# Logic_Gates.net
KiCad netlist of a schematic drawn in EAGLE
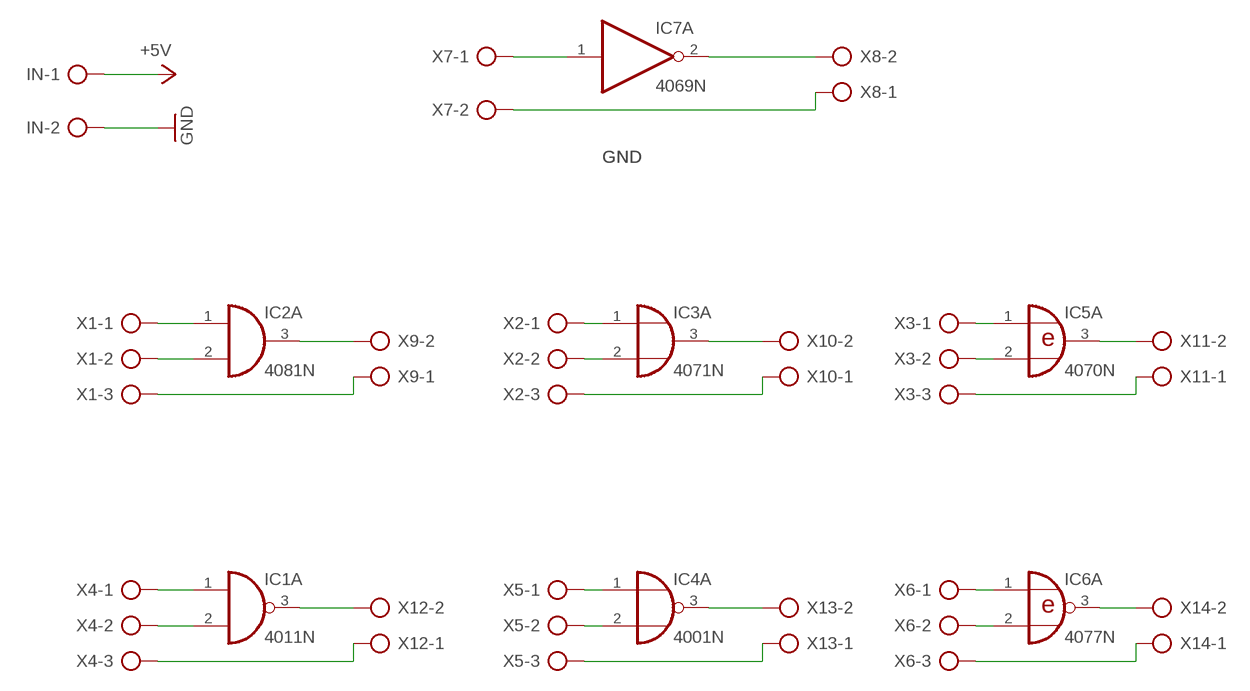
[diagram p0: schematic, sheet 1]

(export (version "E")
  (design (tool "Eeschema 10.0.6"))
  (components
    (comp (ref "IC1")
      (value "4011N")
      (footprint "eagle-import:DIL14")
      (libsource (lib "eagle-import") (part "4011N"))
    )
    (comp (ref "IC2")
      (value "4081N")
      (footprint "eagle-import:DIL14")
      (libsource (lib "eagle-import") (part "4081N"))
    )
    (comp (ref "IC3")
      (value "4071N")
      (footprint "eagle-import:DIL14")
      (libsource (lib "eagle-import") (part "4071N"))
    )
    (comp (ref "IC4")
      (value "4001N")
      (footprint "eagle-import:DIL14")
      (libsource (lib "eagle-import") (part "4001N"))
    )
    (comp (ref "IC5")
      (value "4070N")
      (footprint "eagle-import:DIL14")
      (libsource (lib "eagle-import") (part "4070N"))
    )
    (comp (ref "IC6")
      (value "4077N")
      (footprint "eagle-import:DIL14")
      (libsource (lib "eagle-import") (part "4077N"))
    )
    (comp (ref "IC7")
      (value "4069N")
      (footprint "eagle-import:DIL14")
      (libsource (lib "eagle-import") (part "4069N"))
    )
    (comp (ref "IN")
      (value "AK300/2")
      (footprint "eagle-import:AK300_2")
      (libsource (lib "eagle-import") (part "AK300/2"))
    )
    (comp (ref "X1")
      (value "AK300/3")
      (footprint "eagle-import:AK300_3")
      (libsource (lib "eagle-import") (part "AK300/3"))
    )
    (comp (ref "X2")
      (value "AK300/3")
      (footprint "eagle-import:AK300_3")
      (libsource (lib "eagle-import") (part "AK300/3"))
    )
    (comp (ref "X3")
      (value "AK300/3")
      (footprint "eagle-import:AK300_3")
      (libsource (lib "eagle-import") (part "AK300/3"))
    )
    (comp (ref "X4")
      (value "AK300/3")
      (footprint "eagle-import:AK300_3")
      (libsource (lib "eagle-import") (part "AK300/3"))
    )
    (comp (ref "X5")
      (value "AK300/3")
      (footprint "eagle-import:AK300_3")
      (libsource (lib "eagle-import") (part "AK300/3"))
    )
    (comp (ref "X6")
      (value "AK300/3")
      (footprint "eagle-import:AK300_3")
      (libsource (lib "eagle-import") (part "AK300/3"))
    )
    (comp (ref "X7")
      (value "AK300/2")
      (footprint "eagle-import:AK300_2")
      (libsource (lib "eagle-import") (part "AK300/2"))
    )
    (comp (ref "X8")
      (value "AK300/2")
      (footprint "eagle-import:AK300_2")
      (libsource (lib "eagle-import") (part "AK300/2"))
    )
    (comp (ref "X9")
      (value "AK300/2")
      (footprint "eagle-import:AK300_2")
      (libsource (lib "eagle-import") (part "AK300/2"))
    )
    (comp (ref "X10")
      (value "AK300/2")
      (footprint "eagle-import:AK300_2")
      (libsource (lib "eagle-import") (part "AK300/2"))
    )
    (comp (ref "X11")
      (value "AK300/2")
      (footprint "eagle-import:AK300_2")
      (libsource (lib "eagle-import") (part "AK300/2"))
    )
    (comp (ref "X12")
      (value "AK300/2")
      (footprint "eagle-import:AK300_2")
      (libsource (lib "eagle-import") (part "AK300/2"))
    )
    (comp (ref "X13")
      (value "AK300/2")
      (footprint "eagle-import:AK300_2")
      (libsource (lib "eagle-import") (part "AK300/2"))
    )
    (comp (ref "X14")
      (value "AK300/2")
      (footprint "eagle-import:AK300_2")
      (libsource (lib "eagle-import") (part "AK300/2"))
    )
  )
  (nets
    (net (code "1") (name "+5V") (class "Default")
      (node (ref "IN") (pin "1") (pinfunction "KL_1") (pintype "passive"))
    )
    (net (code "2") (name "GND") (class "Default")
      (node (ref "IN") (pin "2") (pinfunction "KL_2") (pintype "passive"))
      (node (ref "X1") (pin "3") (pinfunction "KL_3") (pintype "passive"))
      (node (ref "X10") (pin "1") (pinfunction "KL_1") (pintype "passive"))
      (node (ref "X11") (pin "1") (pinfunction "KL_1") (pintype "passive"))
      (node (ref "X12") (pin "1") (pinfunction "KL_1") (pintype "passive"))
      (node (ref "X13") (pin "1") (pinfunction "KL_1") (pintype "passive"))
      (node (ref "X14") (pin "1") (pinfunction "KL_1") (pintype "passive"))
      (node (ref "X2") (pin "3") (pinfunction "KL_3") (pintype "passive"))
      (node (ref "X3") (pin "3") (pinfunction "KL_3") (pintype "passive"))
      (node (ref "X4") (pin "3") (pinfunction "KL_3") (pintype "passive"))
      (node (ref "X5") (pin "3") (pinfunction "KL_3") (pintype "passive"))
      (node (ref "X6") (pin "3") (pinfunction "KL_3") (pintype "passive"))
      (node (ref "X7") (pin "2") (pinfunction "KL_2") (pintype "passive"))
      (node (ref "X8") (pin "1") (pinfunction "KL_1") (pintype "passive"))
      (node (ref "X9") (pin "1") (pinfunction "KL_1") (pintype "passive"))
    )
    (net (code "3") (name "Net-(IC1A-I0)") (class "Default")
      (node (ref "IC1") (pin "1") (pinfunction "I0_1") (pintype "input"))
      (node (ref "X4") (pin "1") (pinfunction "KL_1") (pintype "passive"))
    )
    (net (code "4") (name "Net-(IC1A-I1)") (class "Default")
      (node (ref "IC1") (pin "2") (pinfunction "I1_2") (pintype "input"))
      (node (ref "X4") (pin "2") (pinfunction "KL_2") (pintype "passive"))
    )
    (net (code "5") (name "Net-(IC1A-O)") (class "Default")
      (node (ref "IC1") (pin "3") (pinfunction "O_3") (pintype "output"))
      (node (ref "X12") (pin "2") (pinfunction "KL_2") (pintype "passive"))
    )
    (net (code "6") (name "Net-(IC2A-I0)") (class "Default")
      (node (ref "IC2") (pin "1") (pinfunction "I0_1") (pintype "input"))
      (node (ref "X1") (pin "1") (pinfunction "KL_1") (pintype "passive"))
    )
    (net (code "7") (name "Net-(IC2A-I1)") (class "Default")
      (node (ref "IC2") (pin "2") (pinfunction "I1_2") (pintype "input"))
      (node (ref "X1") (pin "2") (pinfunction "KL_2") (pintype "passive"))
    )
    (net (code "8") (name "Net-(IC2A-O)") (class "Default")
      (node (ref "IC2") (pin "3") (pinfunction "O_3") (pintype "output"))
      (node (ref "X9") (pin "2") (pinfunction "KL_2") (pintype "passive"))
    )
    (net (code "9") (name "Net-(IC3A-I0)") (class "Default")
      (node (ref "IC3") (pin "1") (pinfunction "I0_1") (pintype "input"))
      (node (ref "X2") (pin "1") (pinfunction "KL_1") (pintype "passive"))
    )
    (net (code "10") (name "Net-(IC3A-I1)") (class "Default")
      (node (ref "IC3") (pin "2") (pinfunction "I1_2") (pintype "input"))
      (node (ref "X2") (pin "2") (pinfunction "KL_2") (pintype "passive"))
    )
    (net (code "11") (name "Net-(IC3A-O)") (class "Default")
      (node (ref "IC3") (pin "3") (pinfunction "O_3") (pintype "output"))
      (node (ref "X10") (pin "2") (pinfunction "KL_2") (pintype "passive"))
    )
    (net (code "12") (name "Net-(IC4A-I0)") (class "Default")
      (node (ref "IC4") (pin "1") (pinfunction "I0_1") (pintype "input"))
      (node (ref "X5") (pin "1") (pinfunction "KL_1") (pintype "passive"))
    )
    (net (code "13") (name "Net-(IC4A-I1)") (class "Default")
      (node (ref "IC4") (pin "2") (pinfunction "I1_2") (pintype "input"))
      (node (ref "X5") (pin "2") (pinfunction "KL_2") (pintype "passive"))
    )
    (net (code "14") (name "Net-(IC4A-O)") (class "Default")
      (node (ref "IC4") (pin "3") (pinfunction "O_3") (pintype "output"))
      (node (ref "X13") (pin "2") (pinfunction "KL_2") (pintype "passive"))
    )
    (net (code "15") (name "Net-(IC5A-I0)") (class "Default")
      (node (ref "IC5") (pin "1") (pinfunction "I0_1") (pintype "input"))
      (node (ref "X3") (pin "1") (pinfunction "KL_1") (pintype "passive"))
    )
    (net (code "16") (name "Net-(IC5A-I1)") (class "Default")
      (node (ref "IC5") (pin "2") (pinfunction "I1_2") (pintype "input"))
      (node (ref "X3") (pin "2") (pinfunction "KL_2") (pintype "passive"))
    )
    (net (code "17") (name "Net-(IC5A-O)") (class "Default")
      (node (ref "IC5") (pin "3") (pinfunction "O_3") (pintype "output"))
      (node (ref "X11") (pin "2") (pinfunction "KL_2") (pintype "passive"))
    )
    (net (code "18") (name "Net-(IC6A-I0)") (class "Default")
      (node (ref "IC6") (pin "1") (pinfunction "I0_1") (pintype "input"))
      (node (ref "X6") (pin "1") (pinfunction "KL_1") (pintype "passive"))
    )
    (net (code "19") (name "Net-(IC6A-I1)") (class "Default")
      (node (ref "IC6") (pin "2") (pinfunction "I1_2") (pintype "input"))
      (node (ref "X6") (pin "2") (pinfunction "KL_2") (pintype "passive"))
    )
    (net (code "20") (name "Net-(IC6A-O)") (class "Default")
      (node (ref "IC6") (pin "3") (pinfunction "O_3") (pintype "output"))
      (node (ref "X14") (pin "2") (pinfunction "KL_2") (pintype "passive"))
    )
    (net (code "21") (name "Net-(IC7A-I)") (class "Default")
      (node (ref "IC7") (pin "1") (pinfunction "I_1") (pintype "input"))
      (node (ref "X7") (pin "1") (pinfunction "KL_1") (pintype "passive"))
    )
    (net (code "22") (name "Net-(IC7A-O)") (class "Default")
      (node (ref "IC7") (pin "2") (pinfunction "O_2") (pintype "output"))
      (node (ref "X8") (pin "2") (pinfunction "KL_2") (pintype "passive"))
    )
  )
)
